# SerialSD.net
KiCad netlist of a schematic drawn in EAGLE
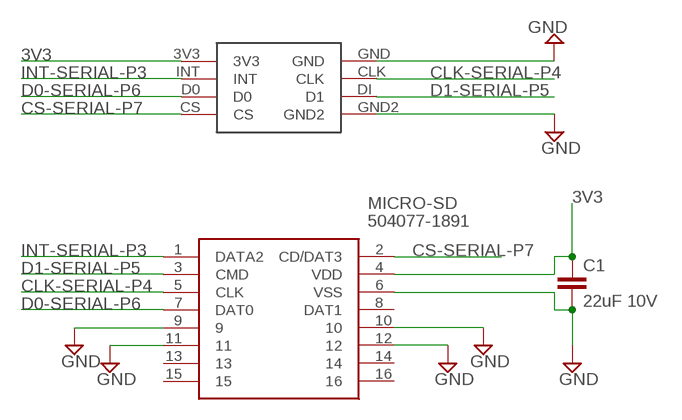
[diagram p0: schematic, sheet 1]

(export (version "E")
  (design (tool "Eeschema 10.0.6"))
  (components
    (comp (ref "C1")
      (value "22uF 10V")
      (footprint "eagle-import:C0805")
      (libsource (lib "eagle-import") (part "C-EUC0805"))
    )
    (comp (ref "MICRO-SD")
      (value "504077-1891")
      (footprint "eagle-import:5040771891")
      (fields (field (name "MOUSER_PART_NUMBER") "538-504077-1891") (field (name "RS_PART_NUMBER") "7768306"))
      (libsource (lib "eagle-import") (part "504077-1891"))
    )
    (comp (ref "U$1")
      (value "SERAIL1")
      (footprint "eagle-import:SERIAL1")
      (libsource (lib "eagle-import") (part "SERAIL1"))
    )
  )
  (nets
    (net (code "1") (name "/3V3") (class "Default")
      (node (ref "C1") (pin "1") (pinfunction "1_1") (pintype "passive"))
      (node (ref "MICRO-SD") (pin "4") (pinfunction "VDD_4") (pintype "power_in"))
      (node (ref "U$1") (pin "3V3") (pinfunction "3V3_3V3") (pintype "bidirectional"))
    )
    (net (code "2") (name "/CLK-SERIAL-P4") (class "Default")
      (node (ref "MICRO-SD") (pin "5") (pinfunction "CLK_5") (pintype "input"))
      (node (ref "U$1") (pin "CLK") (pinfunction "CLK_CLK") (pintype "bidirectional"))
    )
    (net (code "3") (name "/CS-SERIAL-P7") (class "Default")
      (node (ref "MICRO-SD") (pin "2") (pinfunction "CD/DAT3_2") (pintype "bidirectional"))
      (node (ref "U$1") (pin "CS") (pinfunction "CS_CS") (pintype "bidirectional"))
    )
    (net (code "4") (name "/D0-SERIAL-P6") (class "Default")
      (node (ref "MICRO-SD") (pin "7") (pinfunction "DAT0_7") (pintype "bidirectional"))
      (node (ref "U$1") (pin "D0") (pinfunction "D0_D0") (pintype "bidirectional"))
    )
    (net (code "5") (name "/D1-SERIAL-P5") (class "Default")
      (node (ref "MICRO-SD") (pin "3") (pinfunction "CMD_3") (pintype "bidirectional"))
      (node (ref "U$1") (pin "DI") (pinfunction "D1_DI") (pintype "bidirectional"))
    )
    (net (code "6") (name "/INT-SERIAL-P3") (class "Default")
      (node (ref "MICRO-SD") (pin "1") (pinfunction "DATA2_1") (pintype "bidirectional"))
      (node (ref "U$1") (pin "INT") (pinfunction "INT_INT") (pintype "bidirectional"))
    )
    (net (code "7") (name "GND") (class "Default")
      (node (ref "C1") (pin "2") (pinfunction "2_2") (pintype "passive"))
      (node (ref "MICRO-SD") (pin "10") (pinfunction "10_10") (pintype "bidirectional"))
      (node (ref "MICRO-SD") (pin "11") (pinfunction "11_11") (pintype "bidirectional"))
      (node (ref "MICRO-SD") (pin "12") (pinfunction "12_12") (pintype "bidirectional"))
      (node (ref "MICRO-SD") (pin "6") (pinfunction "VSS_6") (pintype "power_in"))
      (node (ref "MICRO-SD") (pin "9") (pinfunction "9_9") (pintype "bidirectional"))
      (node (ref "U$1") (pin "GND") (pinfunction "GND_GND") (pintype "bidirectional"))
      (node (ref "U$1") (pin "GND2") (pinfunction "GND2_GND2") (pintype "bidirectional"))
    )
    (net (code "8") (name "unconnected-(MICRO-SD-DAT1-Pad8)") (class "Default")
      (node (ref "MICRO-SD") (pin "8") (pinfunction "DAT1_8") (pintype "bidirectional"))
    )
    (net (code "9") (name "unconnected-(MICRO-SD-Pad13)") (class "Default")
      (node (ref "MICRO-SD") (pin "13") (pinfunction "13_13") (pintype "bidirectional"))
    )
    (net (code "10") (name "unconnected-(MICRO-SD-Pad14)") (class "Default")
      (node (ref "MICRO-SD") (pin "14") (pinfunction "14_14") (pintype "bidirectional"))
    )
    (net (code "11") (name "unconnected-(MICRO-SD-Pad15)") (class "Default")
      (node (ref "MICRO-SD") (pin "15") (pinfunction "15_15") (pintype "bidirectional"))
    )
    (net (code "12") (name "unconnected-(MICRO-SD-Pad16)") (class "Default")
      (node (ref "MICRO-SD") (pin "16") (pinfunction "16_16") (pintype "bidirectional"))
    )
  )
)
